# scheme1.net
KiCad netlist of a schematic drawn in EAGLE
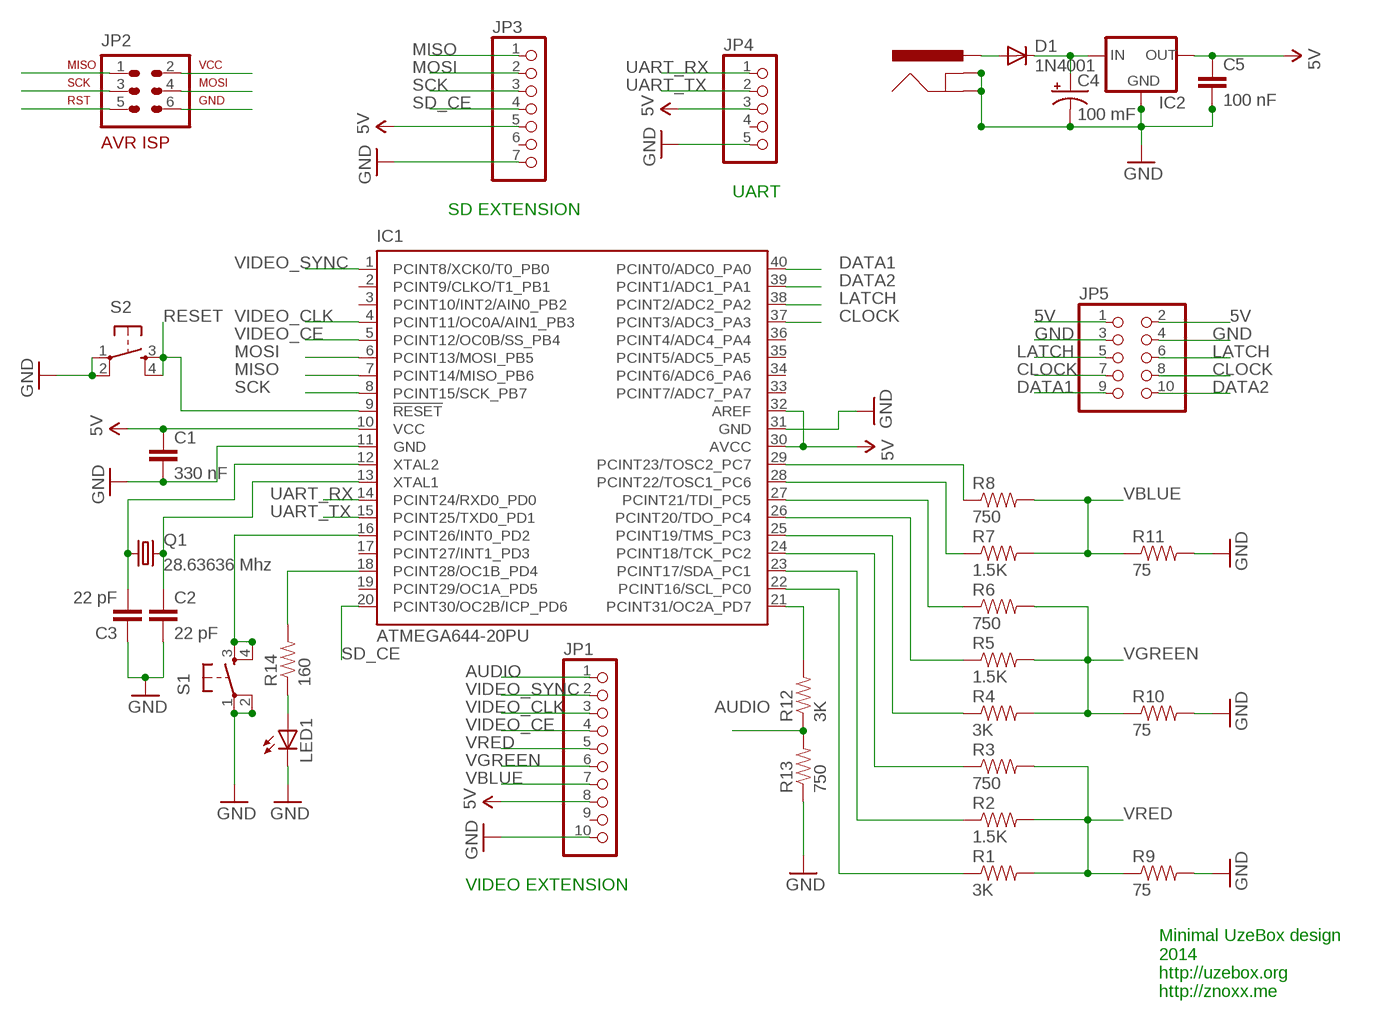
[diagram p0: schematic, sheet 1]

(export (version "E")
  (design (tool "Eeschema 10.0.6"))
  (components
    (comp (ref "C1")
      (value "330 nF")
      (footprint "eagle-import:CAP-PTH-SMALL")
      (libsource (lib "eagle-import") (part "SparkFun-Capacitors_CAPPTH"))
    )
    (comp (ref "C2")
      (value "22 pF")
      (footprint "eagle-import:CAP-PTH-SMALL")
      (libsource (lib "eagle-import") (part "CAPPTH"))
    )
    (comp (ref "C3")
      (value "22 pF")
      (footprint "eagle-import:CAP-PTH-SMALL")
      (libsource (lib "eagle-import") (part "CAPPTH"))
    )
    (comp (ref "C4")
      (value "100 mF")
      (footprint "eagle-import:CPOL-RADIAL-10UF-25V")
      (libsource (lib "eagle-import") (part "CAP_POLPTH2"))
    )
    (comp (ref "C5")
      (value "100 nF")
      (footprint "eagle-import:CAP-PTH-SMALL")
      (libsource (lib "eagle-import") (part "CAPPTH"))
    )
    (comp (ref "D1")
      (value "1N4001")
      (footprint "eagle-import:DIODE-1N4001")
      (libsource (lib "eagle-import") (part "DIODEPTH"))
    )
    (comp (ref "IC1")
      (value "ATMEGA644-20PU")
      (footprint "eagle-import:DIL40")
      (libsource (lib "eagle-import") (part "ATMEGA644-PU20"))
    )
    (comp (ref "IC2")
      (value "V_REG_78XXSIDE")
      (footprint "eagle-import:78XXL")
      (libsource (lib "eagle-import") (part "V_REG_78XXSIDE"))
    )
    (comp (ref "J1")
      (value "POWER_JACKSLT")
      (footprint "eagle-import:POWER_JACK_SLOT")
      (libsource (lib "eagle-import") (part "POWER_JACKSLT"))
    )
    (comp (ref "JP1")
      (value "PINHD-1X10")
      (footprint "eagle-import:1X10")
      (libsource (lib "eagle-import") (part "PINHD-1X10"))
    )
    (comp (ref "JP2")
      (value "AVR-ISP-6VERT")
      (footprint "eagle-import:AVR-ISP-6")
      (libsource (lib "eagle-import") (part "AVR-ISP-6VERT"))
    )
    (comp (ref "JP3")
      (value "PINHD-1X7")
      (footprint "eagle-import:1X07")
      (libsource (lib "eagle-import") (part "PINHD-1X7"))
    )
    (comp (ref "JP4")
      (value "PINHD-1X5")
      (footprint "eagle-import:1X05")
      (libsource (lib "eagle-import") (part "PINHD-1X5"))
    )
    (comp (ref "JP5")
      (value "PINHD-2X5")
      (footprint "eagle-import:2X05")
      (libsource (lib "eagle-import") (part "PINHD-2X5"))
    )
    (comp (ref "LED1")
      (value "LED3MM")
      (footprint "eagle-import:LED3MM")
      (libsource (lib "eagle-import") (part "LED3MM"))
    )
    (comp (ref "Q1")
      (value "28.63636 Mhz")
      (footprint "eagle-import:HC49US")
      (libsource (lib "eagle-import") (part "CRYSTALHC49US"))
    )
    (comp (ref "R1")
      (value "3K")
      (footprint "eagle-import:AXIAL-0.3")
      (libsource (lib "eagle-import") (part "RESISTORPTH1"))
    )
    (comp (ref "R2")
      (value "1.5K")
      (footprint "eagle-import:AXIAL-0.3")
      (libsource (lib "eagle-import") (part "RESISTORPTH1"))
    )
    (comp (ref "R3")
      (value "750")
      (footprint "eagle-import:AXIAL-0.3")
      (libsource (lib "eagle-import") (part "RESISTORPTH1"))
    )
    (comp (ref "R4")
      (value "3K")
      (footprint "eagle-import:AXIAL-0.3")
      (libsource (lib "eagle-import") (part "RESISTORPTH1"))
    )
    (comp (ref "R5")
      (value "1.5K")
      (footprint "eagle-import:AXIAL-0.3")
      (libsource (lib "eagle-import") (part "RESISTORPTH1"))
    )
    (comp (ref "R6")
      (value "750")
      (footprint "eagle-import:AXIAL-0.3")
      (libsource (lib "eagle-import") (part "RESISTORPTH1"))
    )
    (comp (ref "R7")
      (value "1.5K")
      (footprint "eagle-import:AXIAL-0.3")
      (libsource (lib "eagle-import") (part "RESISTORPTH1"))
    )
    (comp (ref "R8")
      (value "750")
      (footprint "eagle-import:AXIAL-0.3")
      (libsource (lib "eagle-import") (part "RESISTORPTH1"))
    )
    (comp (ref "R9")
      (value "75")
      (footprint "eagle-import:AXIAL-0.3")
      (libsource (lib "eagle-import") (part "RESISTORPTH1"))
    )
    (comp (ref "R10")
      (value "75")
      (footprint "eagle-import:AXIAL-0.3")
      (libsource (lib "eagle-import") (part "RESISTORPTH1"))
    )
    (comp (ref "R11")
      (value "75")
      (footprint "eagle-import:AXIAL-0.3")
      (libsource (lib "eagle-import") (part "RESISTORPTH1"))
    )
    (comp (ref "R12")
      (value "3K")
      (footprint "eagle-import:AXIAL-0.3")
      (libsource (lib "eagle-import") (part "RESISTORPTH1"))
    )
    (comp (ref "R13")
      (value "750")
      (footprint "eagle-import:AXIAL-0.3")
      (libsource (lib "eagle-import") (part "RESISTORPTH1"))
    )
    (comp (ref "R14")
      (value "160")
      (footprint "eagle-import:AXIAL-0.3")
      (libsource (lib "eagle-import") (part "RESISTORPTH1"))
    )
    (comp (ref "S1")
      (value "TAC_SWITCHPTH")
      (footprint "eagle-import:TACTILE-PTH")
      (libsource (lib "eagle-import") (part "TAC_SWITCHPTH"))
    )
    (comp (ref "S2")
      (value "TAC_SWITCHPTH")
      (footprint "eagle-import:TACTILE-PTH")
      (libsource (lib "eagle-import") (part "TAC_SWITCHPTH"))
    )
  )
  (nets
    (net (code "1") (name "/AUDIO") (class "Default")
      (node (ref "JP1") (pin "1") (pinfunction "1_1") (pintype "passive"))
      (node (ref "R12") (pin "P$1") (pinfunction "1_P$1") (pintype "passive"))
      (node (ref "R13") (pin "P$2") (pinfunction "2_P$2") (pintype "passive"))
    )
    (net (code "2") (name "/CLOCK") (class "Default")
      (node (ref "IC1") (pin "37") (pinfunction "PCINT3/ADC3_PA3_37") (pintype "bidirectional"))
      (node (ref "JP5") (pin "7") (pinfunction "7_7") (pintype "passive"))
      (node (ref "JP5") (pin "8") (pinfunction "8_8") (pintype "passive"))
    )
    (net (code "3") (name "/DATA1") (class "Default")
      (node (ref "IC1") (pin "40") (pinfunction "PCINT0/ADC0_PA0_40") (pintype "bidirectional"))
      (node (ref "JP5") (pin "9") (pinfunction "9_9") (pintype "passive"))
    )
    (net (code "4") (name "/DATA2") (class "Default")
      (node (ref "IC1") (pin "39") (pinfunction "PCINT1/ADC1_PA1_39") (pintype "bidirectional"))
      (node (ref "JP5") (pin "10") (pinfunction "10_10") (pintype "passive"))
    )
    (net (code "5") (name "/LATCH") (class "Default")
      (node (ref "IC1") (pin "38") (pinfunction "PCINT2/ADC2_PA2_38") (pintype "bidirectional"))
      (node (ref "JP5") (pin "5") (pinfunction "5_5") (pintype "passive"))
      (node (ref "JP5") (pin "6") (pinfunction "6_6") (pintype "passive"))
    )
    (net (code "6") (name "/MISO") (class "Default")
      (node (ref "IC1") (pin "7") (pinfunction "PCINT14/MISO_PB6_7") (pintype "bidirectional"))
      (node (ref "JP2") (pin "1") (pinfunction "1_1") (pintype "passive"))
      (node (ref "JP3") (pin "1") (pinfunction "1_1") (pintype "passive"))
    )
    (net (code "7") (name "/MOSI") (class "Default")
      (node (ref "IC1") (pin "6") (pinfunction "PCINT13/MOSI_PB5_6") (pintype "bidirectional"))
      (node (ref "JP2") (pin "4") (pinfunction "4_4") (pintype "passive"))
      (node (ref "JP3") (pin "2") (pinfunction "2_2") (pintype "passive"))
    )
    (net (code "8") (name "/RESET") (class "Default")
      (node (ref "IC1") (pin "9") (pinfunction "~{RESET}_9") (pintype "input"))
      (node (ref "JP2") (pin "5") (pinfunction "5_5") (pintype "passive"))
      (node (ref "S2") (pin "3") (pinfunction "3_3") (pintype "passive"))
      (node (ref "S2") (pin "4") (pinfunction "4_4") (pintype "passive"))
    )
    (net (code "9") (name "/SCK") (class "Default")
      (node (ref "IC1") (pin "8") (pinfunction "PCINT15/SCK_PB7_8") (pintype "bidirectional"))
      (node (ref "JP2") (pin "3") (pinfunction "3_3") (pintype "passive"))
      (node (ref "JP3") (pin "3") (pinfunction "3_3") (pintype "passive"))
    )
    (net (code "10") (name "/SD_CE") (class "Default")
      (node (ref "IC1") (pin "20") (pinfunction "PCINT30/OC2B/ICP_PD6_20") (pintype "bidirectional"))
      (node (ref "JP3") (pin "4") (pinfunction "4_4") (pintype "passive"))
    )
    (net (code "11") (name "/UART_RX") (class "Default")
      (node (ref "IC1") (pin "14") (pinfunction "PCINT24/RXD0_PD0_14") (pintype "bidirectional"))
      (node (ref "JP4") (pin "1") (pinfunction "1_1") (pintype "passive"))
    )
    (net (code "12") (name "/UART_TX") (class "Default")
      (node (ref "IC1") (pin "15") (pinfunction "PCINT25/TXD0_PD1_15") (pintype "bidirectional"))
      (node (ref "JP4") (pin "2") (pinfunction "2_2") (pintype "passive"))
    )
    (net (code "13") (name "/VBLUE") (class "Default")
      (node (ref "JP1") (pin "7") (pinfunction "7_7") (pintype "passive"))
      (node (ref "R11") (pin "P$1") (pinfunction "1_P$1") (pintype "passive"))
      (node (ref "R7") (pin "P$2") (pinfunction "2_P$2") (pintype "passive"))
      (node (ref "R8") (pin "P$2") (pinfunction "2_P$2") (pintype "passive"))
    )
    (net (code "14") (name "/VGREEN") (class "Default")
      (node (ref "JP1") (pin "6") (pinfunction "6_6") (pintype "passive"))
      (node (ref "R10") (pin "P$1") (pinfunction "1_P$1") (pintype "passive"))
      (node (ref "R4") (pin "P$2") (pinfunction "2_P$2") (pintype "passive"))
      (node (ref "R5") (pin "P$2") (pinfunction "2_P$2") (pintype "passive"))
      (node (ref "R6") (pin "P$2") (pinfunction "2_P$2") (pintype "passive"))
    )
    (net (code "15") (name "/VIDEO_CE") (class "Default")
      (node (ref "IC1") (pin "5") (pinfunction "PCINT12/OC0B/SS_PB4_5") (pintype "bidirectional"))
      (node (ref "JP1") (pin "4") (pinfunction "4_4") (pintype "passive"))
    )
    (net (code "16") (name "/VIDEO_CLK") (class "Default")
      (node (ref "IC1") (pin "4") (pinfunction "PCINT11/OC0A/AIN1_PB3_4") (pintype "bidirectional"))
      (node (ref "JP1") (pin "3") (pinfunction "3_3") (pintype "passive"))
    )
    (net (code "17") (name "/VIDEO_SYNC") (class "Default")
      (node (ref "IC1") (pin "1") (pinfunction "PCINT8/XCK0/T0_PB0_1") (pintype "bidirectional"))
      (node (ref "JP1") (pin "2") (pinfunction "2_2") (pintype "passive"))
    )
    (net (code "18") (name "/VRED") (class "Default")
      (node (ref "JP1") (pin "5") (pinfunction "5_5") (pintype "passive"))
      (node (ref "R1") (pin "P$2") (pinfunction "2_P$2") (pintype "passive"))
      (node (ref "R2") (pin "P$2") (pinfunction "2_P$2") (pintype "passive"))
      (node (ref "R3") (pin "P$2") (pinfunction "2_P$2") (pintype "passive"))
      (node (ref "R9") (pin "P$1") (pinfunction "1_P$1") (pintype "passive"))
    )
    (net (code "19") (name "5V") (class "Default")
      (node (ref "C1") (pin "1") (pinfunction "1_1") (pintype "passive"))
      (node (ref "C5") (pin "1") (pinfunction "1_1") (pintype "passive"))
      (node (ref "IC1") (pin "10") (pinfunction "VCC_10") (pintype "power_in"))
      (node (ref "IC1") (pin "30") (pinfunction "AVCC_30") (pintype "power_in"))
      (node (ref "IC1") (pin "32") (pinfunction "AREF_32") (pintype "passive"))
      (node (ref "IC2") (pin "OUT") (pinfunction "OUT_OUT") (pintype "output"))
      (node (ref "JP1") (pin "8") (pinfunction "8_8") (pintype "passive"))
      (node (ref "JP2") (pin "2") (pinfunction "2_2") (pintype "passive"))
      (node (ref "JP3") (pin "5") (pinfunction "5_5") (pintype "passive"))
      (node (ref "JP4") (pin "3") (pinfunction "3_3") (pintype "passive"))
      (node (ref "JP5") (pin "1") (pinfunction "1_1") (pintype "passive"))
      (node (ref "JP5") (pin "2") (pinfunction "2_2") (pintype "passive"))
    )
    (net (code "20") (name "GND") (class "Default")
      (node (ref "C1") (pin "2") (pinfunction "2_2") (pintype "passive"))
      (node (ref "C2") (pin "2") (pinfunction "2_2") (pintype "passive"))
      (node (ref "C3") (pin "1") (pinfunction "1_1") (pintype "passive"))
      (node (ref "C4") (pin "2") (pinfunction "-_2") (pintype "passive"))
      (node (ref "C5") (pin "2") (pinfunction "2_2") (pintype "passive"))
      (node (ref "IC1") (pin "11") (pinfunction "GND_11") (pintype "power_in"))
      (node (ref "IC1") (pin "31") (pinfunction "GND_31") (pintype "power_in"))
      (node (ref "IC2") (pin "GND") (pinfunction "GND_GND") (pintype "input"))
      (node (ref "J1") (pin "GND@1") (pinfunction "GNDBREAK_GND@1") (pintype "bidirectional"))
      (node (ref "J1") (pin "GND@2") (pinfunction "GND_GND@2") (pintype "bidirectional"))
      (node (ref "JP1") (pin "10") (pinfunction "10_10") (pintype "passive"))
      (node (ref "JP2") (pin "6") (pinfunction "6_6") (pintype "passive"))
      (node (ref "JP3") (pin "7") (pinfunction "7_7") (pintype "passive"))
      (node (ref "JP4") (pin "5") (pinfunction "5_5") (pintype "passive"))
      (node (ref "JP5") (pin "3") (pinfunction "3_3") (pintype "passive"))
      (node (ref "JP5") (pin "4") (pinfunction "4_4") (pintype "passive"))
      (node (ref "LED1") (pin "K") (pinfunction "C_K") (pintype "passive"))
      (node (ref "R10") (pin "P$2") (pinfunction "2_P$2") (pintype "passive"))
      (node (ref "R11") (pin "P$2") (pinfunction "2_P$2") (pintype "passive"))
      (node (ref "R13") (pin "P$1") (pinfunction "1_P$1") (pintype "passive"))
      (node (ref "R9") (pin "P$2") (pinfunction "2_P$2") (pintype "passive"))
      (node (ref "S1") (pin "1") (pinfunction "1_1") (pintype "passive"))
      (node (ref "S1") (pin "2") (pinfunction "2_2") (pintype "passive"))
      (node (ref "S2") (pin "1") (pinfunction "1_1") (pintype "passive"))
      (node (ref "S2") (pin "2") (pinfunction "2_2") (pintype "passive"))
    )
    (net (code "21") (name "Net-(C4-+)") (class "Default")
      (node (ref "C4") (pin "1") (pinfunction "+_1") (pintype "passive"))
      (node (ref "D1") (pin "C") (pinfunction "C_C") (pintype "passive"))
      (node (ref "IC2") (pin "IN") (pinfunction "IN_IN") (pintype "input"))
    )
    (net (code "22") (name "Net-(D1-PadA)") (class "Default")
      (node (ref "D1") (pin "A") (pinfunction "A_A") (pintype "passive"))
      (node (ref "J1") (pin "PWR") (pinfunction "PWR_PWR") (pintype "bidirectional"))
    )
    (net (code "23") (name "Net-(IC1-PCINT16{slash}SCL_PC0)") (class "Default")
      (node (ref "IC1") (pin "22") (pinfunction "PCINT16/SCL_PC0_22") (pintype "bidirectional"))
      (node (ref "R1") (pin "P$1") (pinfunction "1_P$1") (pintype "passive"))
    )
    (net (code "24") (name "Net-(IC1-PCINT17{slash}SDA_PC1)") (class "Default")
      (node (ref "IC1") (pin "23") (pinfunction "PCINT17/SDA_PC1_23") (pintype "bidirectional"))
      (node (ref "R2") (pin "P$1") (pinfunction "1_P$1") (pintype "passive"))
    )
    (net (code "25") (name "Net-(IC1-PCINT18{slash}TCK_PC2)") (class "Default")
      (node (ref "IC1") (pin "24") (pinfunction "PCINT18/TCK_PC2_24") (pintype "bidirectional"))
      (node (ref "R3") (pin "P$1") (pinfunction "1_P$1") (pintype "passive"))
    )
    (net (code "26") (name "Net-(IC1-PCINT19{slash}TMS_PC3)") (class "Default")
      (node (ref "IC1") (pin "25") (pinfunction "PCINT19/TMS_PC3_25") (pintype "bidirectional"))
      (node (ref "R4") (pin "P$1") (pinfunction "1_P$1") (pintype "passive"))
    )
    (net (code "27") (name "Net-(IC1-PCINT20{slash}TDO_PC4)") (class "Default")
      (node (ref "IC1") (pin "26") (pinfunction "PCINT20/TDO_PC4_26") (pintype "bidirectional"))
      (node (ref "R5") (pin "P$1") (pinfunction "1_P$1") (pintype "passive"))
    )
    (net (code "28") (name "Net-(IC1-PCINT21{slash}TDI_PC5)") (class "Default")
      (node (ref "IC1") (pin "27") (pinfunction "PCINT21/TDI_PC5_27") (pintype "bidirectional"))
      (node (ref "R6") (pin "P$1") (pinfunction "1_P$1") (pintype "passive"))
    )
    (net (code "29") (name "Net-(IC1-PCINT22{slash}TOSC1_PC6)") (class "Default")
      (node (ref "IC1") (pin "28") (pinfunction "PCINT22/TOSC1_PC6_28") (pintype "bidirectional"))
      (node (ref "R7") (pin "P$1") (pinfunction "1_P$1") (pintype "passive"))
    )
    (net (code "30") (name "Net-(IC1-PCINT23{slash}TOSC2_PC7)") (class "Default")
      (node (ref "IC1") (pin "29") (pinfunction "PCINT23/TOSC2_PC7_29") (pintype "bidirectional"))
      (node (ref "R8") (pin "P$1") (pinfunction "1_P$1") (pintype "passive"))
    )
    (net (code "31") (name "Net-(IC1-PCINT26{slash}INT0_PD2)") (class "Default")
      (node (ref "IC1") (pin "16") (pinfunction "PCINT26/INT0_PD2_16") (pintype "bidirectional"))
      (node (ref "S1") (pin "3") (pinfunction "3_3") (pintype "passive"))
      (node (ref "S1") (pin "4") (pinfunction "4_4") (pintype "passive"))
    )
    (net (code "32") (name "Net-(IC1-PCINT28{slash}OC1B_PD4)") (class "Default")
      (node (ref "IC1") (pin "18") (pinfunction "PCINT28/OC1B_PD4_18") (pintype "bidirectional"))
      (node (ref "R14") (pin "P$2") (pinfunction "2_P$2") (pintype "passive"))
    )
    (net (code "33") (name "Net-(IC1-PCINT31{slash}OC2A_PD7)") (class "Default")
      (node (ref "IC1") (pin "21") (pinfunction "PCINT31/OC2A_PD7_21") (pintype "bidirectional"))
      (node (ref "R12") (pin "P$2") (pinfunction "2_P$2") (pintype "passive"))
    )
    (net (code "34") (name "Net-(IC1-XTAL1)") (class "Default")
      (node (ref "C2") (pin "1") (pinfunction "1_1") (pintype "passive"))
      (node (ref "IC1") (pin "13") (pinfunction "XTAL1_13") (pintype "input"))
      (node (ref "Q1") (pin "2") (pinfunction "2_2") (pintype "passive"))
    )
    (net (code "35") (name "Net-(IC1-XTAL2)") (class "Default")
      (node (ref "C3") (pin "2") (pinfunction "2_2") (pintype "passive"))
      (node (ref "IC1") (pin "12") (pinfunction "XTAL2_12") (pintype "output"))
      (node (ref "Q1") (pin "1") (pinfunction "1_1") (pintype "passive"))
    )
    (net (code "36") (name "Net-(R14-1)") (class "Default")
      (node (ref "LED1") (pin "A") (pinfunction "A_A") (pintype "passive"))
      (node (ref "R14") (pin "P$1") (pinfunction "1_P$1") (pintype "passive"))
    )
    (net (code "37") (name "unconnected-(IC1-PCINT4{slash}ADC4_PA4-Pad36)") (class "Default")
      (node (ref "IC1") (pin "36") (pinfunction "PCINT4/ADC4_PA4_36") (pintype "bidirectional"))
    )
    (net (code "38") (name "unconnected-(IC1-PCINT5{slash}ADC5_PA5-Pad35)") (class "Default")
      (node (ref "IC1") (pin "35") (pinfunction "PCINT5/ADC5_PA5_35") (pintype "bidirectional"))
    )
    (net (code "39") (name "unconnected-(IC1-PCINT6{slash}ADC6_PA6-Pad34)") (class "Default")
      (node (ref "IC1") (pin "34") (pinfunction "PCINT6/ADC6_PA6_34") (pintype "bidirectional"))
    )
    (net (code "40") (name "unconnected-(IC1-PCINT7{slash}ADC7_PA7-Pad33)") (class "Default")
      (node (ref "IC1") (pin "33") (pinfunction "PCINT7/ADC7_PA7_33") (pintype "bidirectional"))
    )
    (net (code "41") (name "unconnected-(IC1-PCINT9{slash}CLKO{slash}T1_PB1-Pad2)") (class "Default")
      (node (ref "IC1") (pin "2") (pinfunction "PCINT9/CLKO/T1_PB1_2") (pintype "bidirectional"))
    )
    (net (code "42") (name "unconnected-(IC1-PCINT10{slash}INT2{slash}AIN0_PB2-Pad3)") (class "Default")
      (node (ref "IC1") (pin "3") (pinfunction "PCINT10/INT2/AIN0_PB2_3") (pintype "bidirectional"))
    )
    (net (code "43") (name "unconnected-(IC1-PCINT27{slash}INT1_PD3-Pad17)") (class "Default")
      (node (ref "IC1") (pin "17") (pinfunction "PCINT27/INT1_PD3_17") (pintype "bidirectional"))
    )
    (net (code "44") (name "unconnected-(IC1-PCINT29{slash}OC1A_PD5-Pad19)") (class "Default")
      (node (ref "IC1") (pin "19") (pinfunction "PCINT29/OC1A_PD5_19") (pintype "bidirectional"))
    )
    (net (code "45") (name "unconnected-(JP1-Pad9)") (class "Default")
      (node (ref "JP1") (pin "9") (pinfunction "9_9") (pintype "passive"))
    )
    (net (code "46") (name "unconnected-(JP3-Pad6)") (class "Default")
      (node (ref "JP3") (pin "6") (pinfunction "6_6") (pintype "passive"))
    )
    (net (code "47") (name "unconnected-(JP4-Pad4)") (class "Default")
      (node (ref "JP4") (pin "4") (pinfunction "4_4") (pintype "passive"))
    )
  )
)
